# badge2012.net
KiCad netlist of a schematic drawn in EAGLE
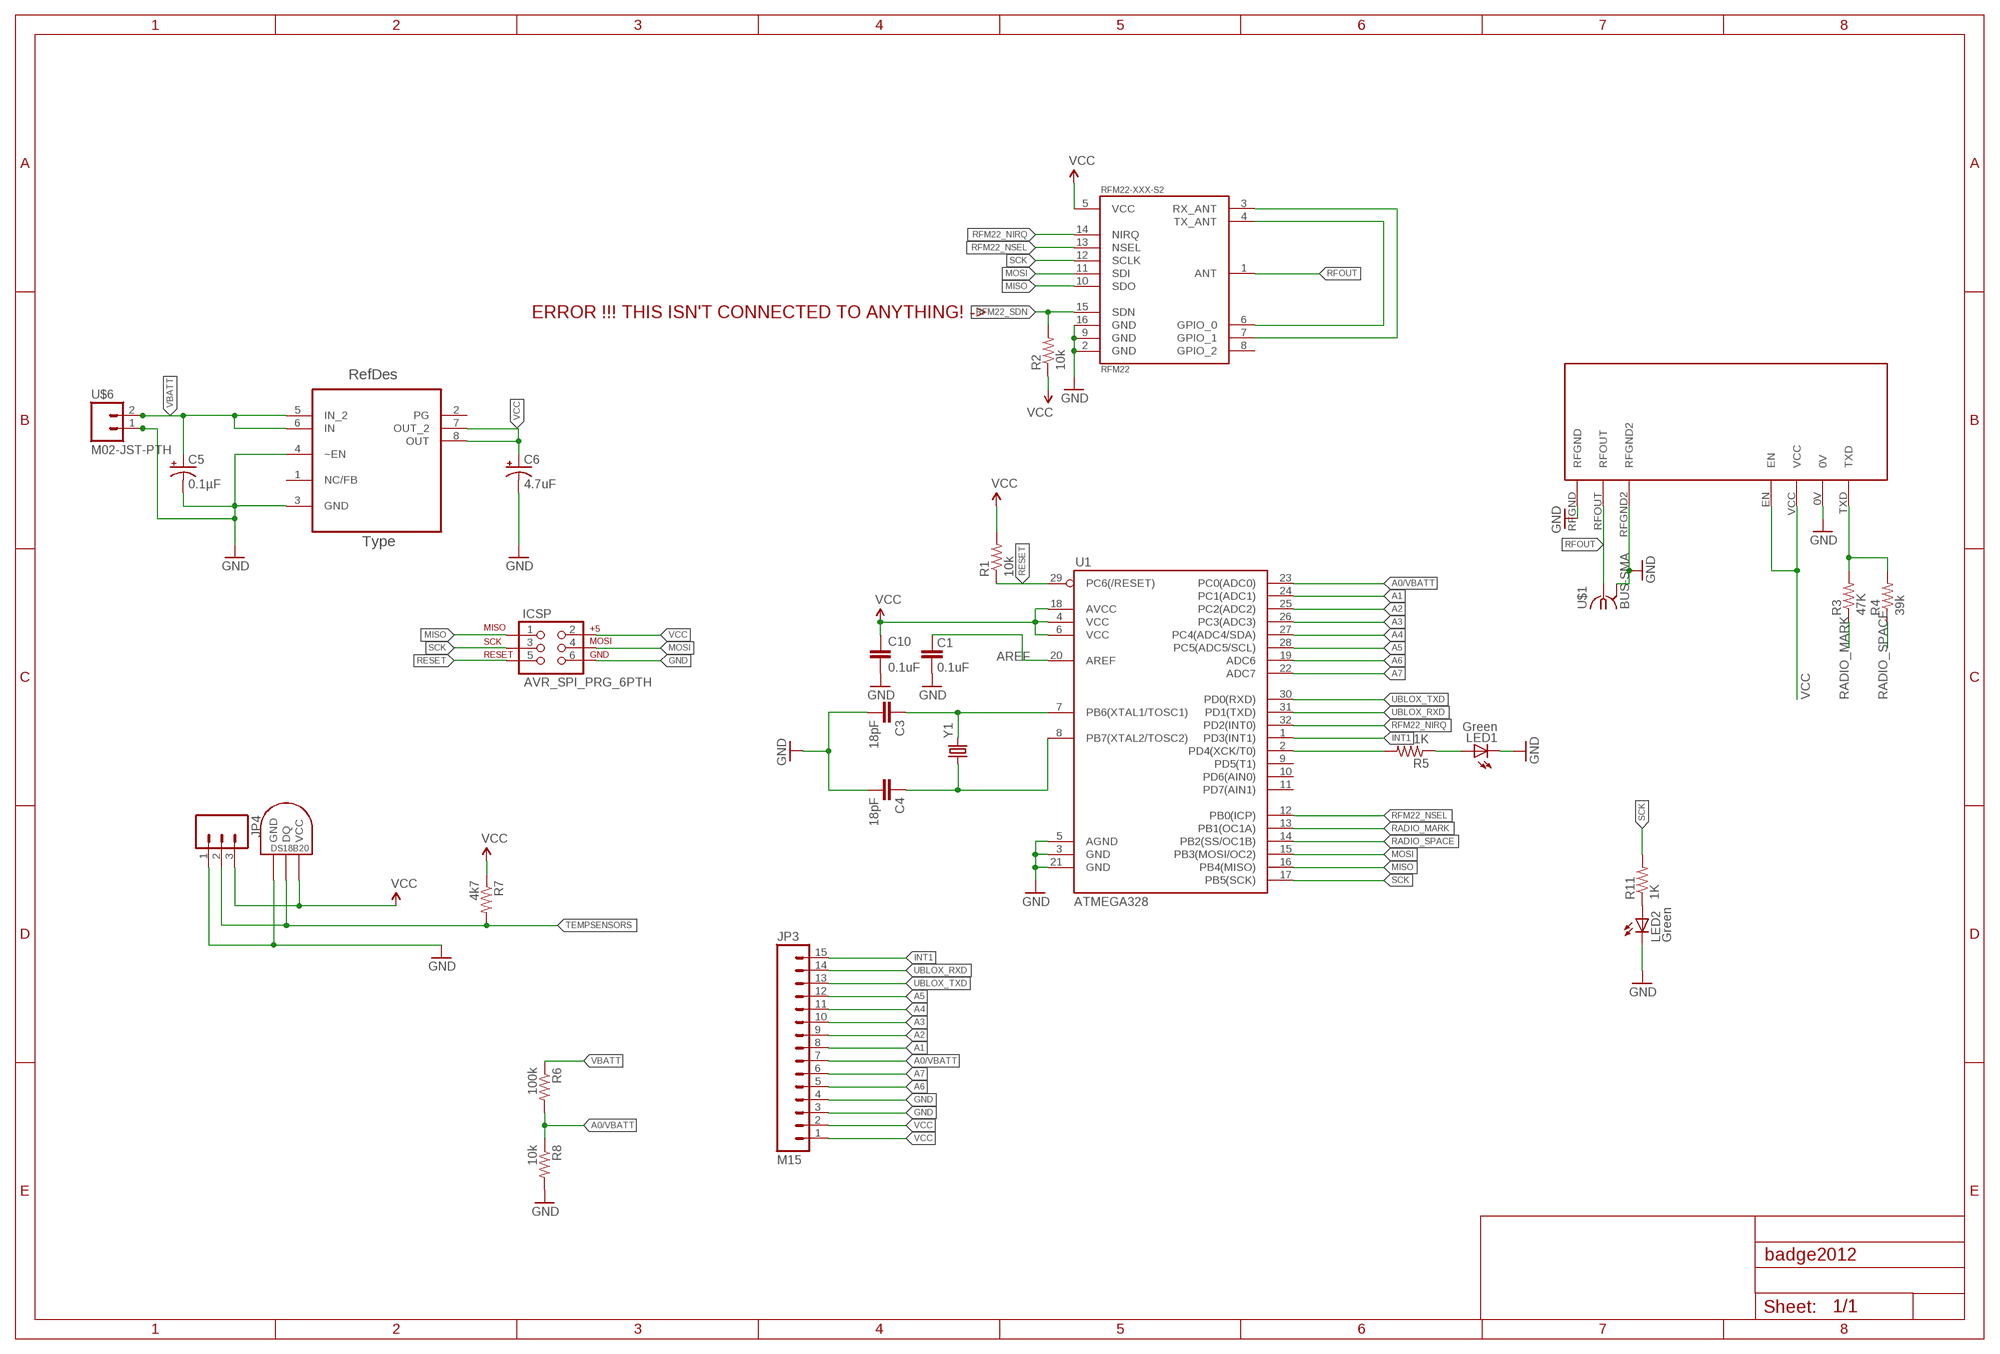
[diagram p0: schematic, sheet 1]

(export (version "E")
  (design (tool "Eeschema 10.0.6"))
  (components
    (comp (ref "C1")
      (value "0.1uF")
      (footprint "eagle-import:0603-CAP")
      (libsource (lib "eagle-import") (part "CAP0603-CAP"))
    )
    (comp (ref "C3")
      (value "18pF")
      (footprint "eagle-import:0603-CAP")
      (libsource (lib "eagle-import") (part "CAP0603-CAP"))
    )
    (comp (ref "C4")
      (value "18pF")
      (footprint "eagle-import:0603-CAP")
      (libsource (lib "eagle-import") (part "CAP0603-CAP"))
    )
    (comp (ref "C5")
      (value "0.1µF")
      (footprint "eagle-import:EIA3216-KIT")
      (libsource (lib "eagle-import") (part "CAP_POL1206-KIT"))
    )
    (comp (ref "C6")
      (value "4.7uF")
      (footprint "eagle-import:EIA3216-KIT")
      (libsource (lib "eagle-import") (part "CAP_POL1206-KIT"))
    )
    (comp (ref "C10")
      (value "0.1uF")
      (footprint "eagle-import:0603-CAP")
      (libsource (lib "eagle-import") (part "CAP0603-CAP"))
    )
    (comp (ref "ICSP")
      (value "AVR_SPI_PRG_6PTH")
      (footprint "eagle-import:2X3")
      (libsource (lib "eagle-import") (part "AVR_SPI_PRG_6PTH"))
    )
    (comp (ref "JP3")
      (value "M15")
      (footprint "eagle-import:1X15")
      (libsource (lib "eagle-import") (part "M15"))
    )
    (comp (ref "JP4")
      (value "M03PTH")
      (footprint "eagle-import:1X03")
      (libsource (lib "eagle-import") (part "M03PTH"))
    )
    (comp (ref "LED1")
      (value "Green")
      (footprint "eagle-import:LED-0603")
      (libsource (lib "eagle-import") (part "LED0603"))
    )
    (comp (ref "LED2")
      (value "Green")
      (footprint "eagle-import:LED-0603")
      (libsource (lib "eagle-import") (part "LED0603"))
    )
    (comp (ref "NTX2TEMP")
      (value "DS1821")
      (footprint "eagle-import:DS18B20_SOIC")
      (libsource (lib "eagle-import") (part "DS1820SOIC"))
    )
    (comp (ref "R1")
      (value "10k")
      (footprint "eagle-import:0603-RES")
      (libsource (lib "eagle-import") (part "RESISTOR0603-RES"))
    )
    (comp (ref "R2")
      (value "10k")
      (footprint "eagle-import:0603-RES")
      (libsource (lib "eagle-import") (part "RESISTOR0603-RES"))
    )
    (comp (ref "R3")
      (value "47K")
      (footprint "eagle-import:0603-RES")
      (libsource (lib "eagle-import") (part "RESISTOR0603-RES"))
    )
    (comp (ref "R4")
      (value "39k")
      (footprint "eagle-import:0603-RES")
      (libsource (lib "eagle-import") (part "RESISTOR0603-RES"))
    )
    (comp (ref "R5")
      (value "1K")
      (footprint "eagle-import:0603-RES")
      (libsource (lib "eagle-import") (part "RESISTOR0603-RES"))
    )
    (comp (ref "R6")
      (value "100k")
      (footprint "eagle-import:0603-RES")
      (libsource (lib "eagle-import") (part "RESISTOR0603-RES"))
    )
    (comp (ref "R7")
      (value "4k7")
      (footprint "eagle-import:0603-RES")
      (libsource (lib "eagle-import") (part "RESISTOR0603-RES"))
    )
    (comp (ref "R8")
      (value "10k")
      (footprint "eagle-import:0603-RES")
      (libsource (lib "eagle-import") (part "RESISTOR0603-RES"))
    )
    (comp (ref "R11")
      (value "1K")
      (footprint "eagle-import:0603-RES")
      (libsource (lib "eagle-import") (part "RESISTOR0603-RES"))
    )
    (comp (ref "RFM22-XXX-S2")
      (value "RFM22")
      (footprint "eagle-import:RFM22-XXX-S2")
      (libsource (lib "eagle-import") (part "RFM22"))
    )
    (comp (ref "U$1")
      (value "BUS-SMA")
      (footprint "eagle-import:BUS-SMA")
      (libsource (lib "eagle-import") (part "BUS-SMA"))
    )
    (comp (ref "U$4")
      (value "NTX2")
      (footprint "eagle-import:NTX2")
      (libsource (lib "eagle-import") (part "NTX2"))
    )
    (comp (ref "U$6")
      (value "M02-JST-PTH")
      (footprint "eagle-import:M02-JST-PTH")
      (libsource (lib "eagle-import") (part "M02-JST-PTH"))
    )
    (comp (ref "U1")
      (value "ATMEGA328")
      (footprint "eagle-import:TQFP32-08")
      (libsource (lib "eagle-import") (part "ATMEGA168"))
    )
    (comp (ref "U2")
      (value "TPS76633D")
      (footprint "eagle-import:SOIC127P600X175-8N")
      (libsource (lib "eagle-import") (part "TPS76633D"))
    )
    (comp (ref "Y1")
      (value "CRYSTALSMD")
      (footprint "eagle-import:HC49UP")
      (libsource (lib "eagle-import") (part "CRYSTALSMD"))
    )
  )
  (nets
    (net (code "1") (name "/AREF") (class "Default")
      (node (ref "C1") (pin "2") (pinfunction "2_2") (pintype "passive"))
      (node (ref "U1") (pin "20") (pinfunction "AREF_20") (pintype "bidirectional"))
    )
    (net (code "2") (name "A0{slash}VBATT") (class "Default")
      (node (ref "JP3") (pin "7") (pinfunction "7_7") (pintype "passive"))
      (node (ref "R6") (pin "2") (pinfunction "2_2") (pintype "passive"))
      (node (ref "R8") (pin "1") (pinfunction "1_1") (pintype "passive"))
      (node (ref "U1") (pin "23") (pinfunction "PC0(ADC0)_23") (pintype "bidirectional"))
    )
    (net (code "3") (name "A1") (class "Default")
      (node (ref "JP3") (pin "8") (pinfunction "8_8") (pintype "passive"))
      (node (ref "U1") (pin "24") (pinfunction "PC1(ADC1)_24") (pintype "bidirectional"))
    )
    (net (code "4") (name "A2") (class "Default")
      (node (ref "JP3") (pin "9") (pinfunction "9_9") (pintype "passive"))
      (node (ref "U1") (pin "25") (pinfunction "PC2(ADC2)_25") (pintype "bidirectional"))
    )
    (net (code "5") (name "A3") (class "Default")
      (node (ref "JP3") (pin "10") (pinfunction "10_10") (pintype "passive"))
      (node (ref "U1") (pin "26") (pinfunction "PC3(ADC3)_26") (pintype "bidirectional"))
    )
    (net (code "6") (name "A4") (class "Default")
      (node (ref "JP3") (pin "11") (pinfunction "11_11") (pintype "passive"))
      (node (ref "U1") (pin "27") (pinfunction "PC4(ADC4/SDA)_27") (pintype "bidirectional"))
    )
    (net (code "7") (name "A5") (class "Default")
      (node (ref "JP3") (pin "12") (pinfunction "12_12") (pintype "passive"))
      (node (ref "U1") (pin "28") (pinfunction "PC5(ADC5/SCL)_28") (pintype "bidirectional"))
    )
    (net (code "8") (name "A6") (class "Default")
      (node (ref "JP3") (pin "5") (pinfunction "5_5") (pintype "passive"))
      (node (ref "U1") (pin "19") (pinfunction "ADC6_19") (pintype "bidirectional"))
    )
    (net (code "9") (name "A7") (class "Default")
      (node (ref "JP3") (pin "6") (pinfunction "6_6") (pintype "passive"))
      (node (ref "U1") (pin "22") (pinfunction "ADC7_22") (pintype "bidirectional"))
    )
    (net (code "10") (name "GND") (class "Default")
      (node (ref "C1") (pin "1") (pinfunction "1_1") (pintype "passive"))
      (node (ref "C10") (pin "2") (pinfunction "2_2") (pintype "passive"))
      (node (ref "C3") (pin "2") (pinfunction "2_2") (pintype "passive"))
      (node (ref "C4") (pin "2") (pinfunction "2_2") (pintype "passive"))
      (node (ref "C5") (pin "C") (pinfunction "-_C") (pintype "passive"))
      (node (ref "C6") (pin "C") (pinfunction "-_C") (pintype "passive"))
      (node (ref "ICSP") (pin "6") (pinfunction "6_6") (pintype "passive"))
      (node (ref "JP3") (pin "3") (pinfunction "3_3") (pintype "passive"))
      (node (ref "JP3") (pin "4") (pinfunction "4_4") (pintype "passive"))
      (node (ref "JP4") (pin "1") (pinfunction "1_1") (pintype "passive"))
      (node (ref "LED1") (pin "C") (pinfunction "C_C") (pintype "passive"))
      (node (ref "LED2") (pin "C") (pinfunction "C_C") (pintype "passive"))
      (node (ref "NTX2TEMP") (pin "GND") (pinfunction "GND_GND") (pintype "power_in"))
      (node (ref "R8") (pin "2") (pinfunction "2_2") (pintype "passive"))
      (node (ref "RFM22-XXX-S2") (pin "16") (pinfunction "GND_16") (pintype "power_in"))
      (node (ref "RFM22-XXX-S2") (pin "2") (pinfunction "GND_2") (pintype "power_in"))
      (node (ref "RFM22-XXX-S2") (pin "9") (pinfunction "GND_9") (pintype "power_in"))
      (node (ref "U$1") (pin "2") (pinfunction "GND_2") (pintype "power_in"))
      (node (ref "U$1") (pin "3") (pinfunction "GND_3") (pintype "power_in"))
      (node (ref "U$1") (pin "4") (pinfunction "GND_4") (pintype "power_in"))
      (node (ref "U$1") (pin "5") (pinfunction "GND_5") (pintype "power_in"))
      (node (ref "U$4") (pin "0V") (pinfunction "0V_0V") (pintype "bidirectional"))
      (node (ref "U$4") (pin "RFGND") (pinfunction "RFGND_RFGND") (pintype "bidirectional"))
      (node (ref "U$4") (pin "RFGND2") (pinfunction "RFGND2_RFGND2") (pintype "bidirectional"))
      (node (ref "U$6") (pin "1") (pinfunction "1_1") (pintype "passive"))
      (node (ref "U1") (pin "21") (pinfunction "GND_21") (pintype "bidirectional"))
      (node (ref "U1") (pin "3") (pinfunction "GND_3") (pintype "bidirectional"))
      (node (ref "U1") (pin "5") (pinfunction "AGND_5") (pintype "bidirectional"))
      (node (ref "U2") (pin "3") (pinfunction "GND_3") (pintype "passive"))
      (node (ref "U2") (pin "4") (pinfunction "~{EN}_4") (pintype "input"))
    )
    (net (code "11") (name "INT1") (class "Default")
      (node (ref "JP3") (pin "15") (pinfunction "15_15") (pintype "passive"))
      (node (ref "U1") (pin "1") (pinfunction "PD3(INT1)_1") (pintype "bidirectional"))
    )
    (net (code "12") (name "MISO") (class "Default")
      (node (ref "ICSP") (pin "1") (pinfunction "1_1") (pintype "passive"))
      (node (ref "RFM22-XXX-S2") (pin "10") (pinfunction "SDO_10") (pintype "output"))
      (node (ref "U1") (pin "16") (pinfunction "PB4(MISO)_16") (pintype "bidirectional"))
    )
    (net (code "13") (name "MOSI") (class "Default")
      (node (ref "ICSP") (pin "4") (pinfunction "4_4") (pintype "passive"))
      (node (ref "RFM22-XXX-S2") (pin "11") (pinfunction "SDI_11") (pintype "input"))
      (node (ref "U1") (pin "15") (pinfunction "PB3(MOSI/OC2)_15") (pintype "bidirectional"))
    )
    (net (code "14") (name "Net-(LED1-PadA)") (class "Default")
      (node (ref "LED1") (pin "A") (pinfunction "A_A") (pintype "passive"))
      (node (ref "R5") (pin "1") (pinfunction "1_1") (pintype "passive"))
    )
    (net (code "15") (name "Net-(LED2-PadA)") (class "Default")
      (node (ref "LED2") (pin "A") (pinfunction "A_A") (pintype "passive"))
      (node (ref "R11") (pin "1") (pinfunction "1_1") (pintype "passive"))
    )
    (net (code "16") (name "Net-(R3-Pad2)") (class "Default")
      (node (ref "R3") (pin "2") (pinfunction "2_2") (pintype "passive"))
      (node (ref "R4") (pin "2") (pinfunction "2_2") (pintype "passive"))
      (node (ref "U$4") (pin "TXD") (pinfunction "TXD_TXD") (pintype "bidirectional"))
    )
    (net (code "17") (name "Net-(RFM22-XXX-S2-GPIO_0)") (class "Default")
      (node (ref "RFM22-XXX-S2") (pin "4") (pinfunction "TX_ANT_4") (pintype "input"))
      (node (ref "RFM22-XXX-S2") (pin "6") (pinfunction "GPIO_0_6") (pintype "bidirectional"))
    )
    (net (code "18") (name "Net-(RFM22-XXX-S2-GPIO_1)") (class "Default")
      (node (ref "RFM22-XXX-S2") (pin "3") (pinfunction "RX_ANT_3") (pintype "input"))
      (node (ref "RFM22-XXX-S2") (pin "7") (pinfunction "GPIO_1_7") (pintype "bidirectional"))
    )
    (net (code "19") (name "Net-(U1-PB6(XTAL1{slash}TOSC1))") (class "Default")
      (node (ref "C3") (pin "1") (pinfunction "1_1") (pintype "passive"))
      (node (ref "U1") (pin "7") (pinfunction "PB6(XTAL1/TOSC1)_7") (pintype "bidirectional"))
      (node (ref "Y1") (pin "2") (pinfunction "2_2") (pintype "passive"))
    )
    (net (code "20") (name "Net-(U1-PB7(XTAL2{slash}TOSC2))") (class "Default")
      (node (ref "C4") (pin "1") (pinfunction "1_1") (pintype "passive"))
      (node (ref "U1") (pin "8") (pinfunction "PB7(XTAL2/TOSC2)_8") (pintype "bidirectional"))
      (node (ref "Y1") (pin "1") (pinfunction "1_1") (pintype "passive"))
    )
    (net (code "21") (name "Net-(U1-PD4(XCK{slash}T0))") (class "Default")
      (node (ref "R5") (pin "2") (pinfunction "2_2") (pintype "passive"))
      (node (ref "U1") (pin "2") (pinfunction "PD4(XCK/T0)_2") (pintype "bidirectional"))
    )
    (net (code "22") (name "RADIO_MARK") (class "Default")
      (node (ref "R3") (pin "1") (pinfunction "1_1") (pintype "passive"))
      (node (ref "U1") (pin "13") (pinfunction "PB1(OC1A)_13") (pintype "bidirectional"))
    )
    (net (code "23") (name "RADIO_SPACE") (class "Default")
      (node (ref "R4") (pin "1") (pinfunction "1_1") (pintype "passive"))
      (node (ref "U1") (pin "14") (pinfunction "PB2(SS/OC1B)_14") (pintype "bidirectional"))
    )
    (net (code "24") (name "RESET") (class "Default")
      (node (ref "ICSP") (pin "5") (pinfunction "5_5") (pintype "passive"))
      (node (ref "R1") (pin "1") (pinfunction "1_1") (pintype "passive"))
      (node (ref "U1") (pin "29") (pinfunction "PC6(/RESET)_29") (pintype "bidirectional"))
    )
    (net (code "25") (name "RFM22_NIRQ") (class "Default")
      (node (ref "RFM22-XXX-S2") (pin "14") (pinfunction "NIRQ_14") (pintype "output"))
      (node (ref "U1") (pin "32") (pinfunction "PD2(INT0)_32") (pintype "bidirectional"))
    )
    (net (code "26") (name "RFM22_NSEL") (class "Default")
      (node (ref "RFM22-XXX-S2") (pin "13") (pinfunction "NSEL_13") (pintype "input"))
      (node (ref "U1") (pin "12") (pinfunction "PB0(ICP)_12") (pintype "bidirectional"))
    )
    (net (code "27") (name "RFM22_SDN") (class "Default")
      (node (ref "R2") (pin "2") (pinfunction "2_2") (pintype "passive"))
      (node (ref "RFM22-XXX-S2") (pin "15") (pinfunction "SDN_15") (pintype "input"))
    )
    (net (code "28") (name "RFOUT") (class "Default")
      (node (ref "RFM22-XXX-S2") (pin "1") (pinfunction "ANT_1") (pintype "bidirectional"))
      (node (ref "U$1") (pin "1") (pinfunction "1_1") (pintype "passive"))
      (node (ref "U$4") (pin "RFOUT") (pinfunction "RFOUT_RFOUT") (pintype "bidirectional"))
    )
    (net (code "29") (name "SCK") (class "Default")
      (node (ref "ICSP") (pin "3") (pinfunction "3_3") (pintype "passive"))
      (node (ref "R11") (pin "2") (pinfunction "2_2") (pintype "passive"))
      (node (ref "RFM22-XXX-S2") (pin "12") (pinfunction "SCLK_12") (pintype "input"))
      (node (ref "U1") (pin "17") (pinfunction "PB5(SCK)_17") (pintype "bidirectional"))
    )
    (net (code "30") (name "TEMPSENSORS") (class "Default")
      (node (ref "JP4") (pin "2") (pinfunction "2_2") (pintype "passive"))
      (node (ref "NTX2TEMP") (pin "DQ") (pinfunction "DQ_DQ") (pintype "bidirectional"))
      (node (ref "R7") (pin "2") (pinfunction "2_2") (pintype "passive"))
    )
    (net (code "31") (name "UBLOX_RXD") (class "Default")
      (node (ref "JP3") (pin "14") (pinfunction "14_14") (pintype "passive"))
      (node (ref "U1") (pin "31") (pinfunction "PD1(TXD)_31") (pintype "bidirectional"))
    )
    (net (code "32") (name "UBLOX_TXD") (class "Default")
      (node (ref "JP3") (pin "13") (pinfunction "13_13") (pintype "passive"))
      (node (ref "U1") (pin "30") (pinfunction "PD0(RXD)_30") (pintype "bidirectional"))
    )
    (net (code "33") (name "VBATT") (class "Default")
      (node (ref "C5") (pin "A") (pinfunction "+_A") (pintype "passive"))
      (node (ref "R6") (pin "1") (pinfunction "1_1") (pintype "passive"))
      (node (ref "U$6") (pin "2") (pinfunction "2_2") (pintype "passive"))
      (node (ref "U2") (pin "5") (pinfunction "IN_2_5") (pintype "input"))
      (node (ref "U2") (pin "6") (pinfunction "IN_6") (pintype "input"))
    )
    (net (code "34") (name "VCC") (class "Default")
      (node (ref "C10") (pin "1") (pinfunction "1_1") (pintype "passive"))
      (node (ref "C6") (pin "A") (pinfunction "+_A") (pintype "passive"))
      (node (ref "ICSP") (pin "2") (pinfunction "2_2") (pintype "passive"))
      (node (ref "JP3") (pin "1") (pinfunction "1_1") (pintype "passive"))
      (node (ref "JP3") (pin "2") (pinfunction "2_2") (pintype "passive"))
      (node (ref "JP4") (pin "3") (pinfunction "3_3") (pintype "passive"))
      (node (ref "NTX2TEMP") (pin "VCC") (pinfunction "VCC_VCC") (pintype "power_in"))
      (node (ref "R1") (pin "2") (pinfunction "2_2") (pintype "passive"))
      (node (ref "R2") (pin "1") (pinfunction "1_1") (pintype "passive"))
      (node (ref "R7") (pin "1") (pinfunction "1_1") (pintype "passive"))
      (node (ref "RFM22-XXX-S2") (pin "5") (pinfunction "VCC_5") (pintype "bidirectional"))
      (node (ref "U$4") (pin "EN") (pinfunction "EN_EN") (pintype "bidirectional"))
      (node (ref "U$4") (pin "VCC") (pinfunction "VCC_VCC") (pintype "bidirectional"))
      (node (ref "U1") (pin "18") (pinfunction "AVCC_18") (pintype "bidirectional"))
      (node (ref "U1") (pin "4") (pinfunction "VCC_4") (pintype "bidirectional"))
      (node (ref "U1") (pin "6") (pinfunction "VCC_6") (pintype "bidirectional"))
      (node (ref "U2") (pin "7") (pinfunction "OUT_2_7") (pintype "output"))
      (node (ref "U2") (pin "8") (pinfunction "OUT_8") (pintype "output"))
    )
    (net (code "35") (name "unconnected-(RFM22-XXX-S2-GPIO_2-Pad8)") (class "Default")
      (node (ref "RFM22-XXX-S2") (pin "8") (pinfunction "GPIO_2_8") (pintype "bidirectional"))
    )
    (net (code "36") (name "unconnected-(U1-PD5(T1)-Pad9)") (class "Default")
      (node (ref "U1") (pin "9") (pinfunction "PD5(T1)_9") (pintype "bidirectional"))
    )
    (net (code "37") (name "unconnected-(U1-PD6(AIN0)-Pad10)") (class "Default")
      (node (ref "U1") (pin "10") (pinfunction "PD6(AIN0)_10") (pintype "bidirectional"))
    )
    (net (code "38") (name "unconnected-(U1-PD7(AIN1)-Pad11)") (class "Default")
      (node (ref "U1") (pin "11") (pinfunction "PD7(AIN1)_11") (pintype "bidirectional"))
    )
    (net (code "39") (name "unconnected-(U2-NC{slash}FB-Pad1)") (class "Default")
      (node (ref "U2") (pin "1") (pinfunction "NC/FB_1") (pintype "no_connect"))
    )
    (net (code "40") (name "unconnected-(U2-PG-Pad2)") (class "Default")
      (node (ref "U2") (pin "2") (pinfunction "PG_2") (pintype "output"))
    )
  )
)
